# nh-vend_v0_1.net
KiCad netlist of a schematic drawn in EAGLE
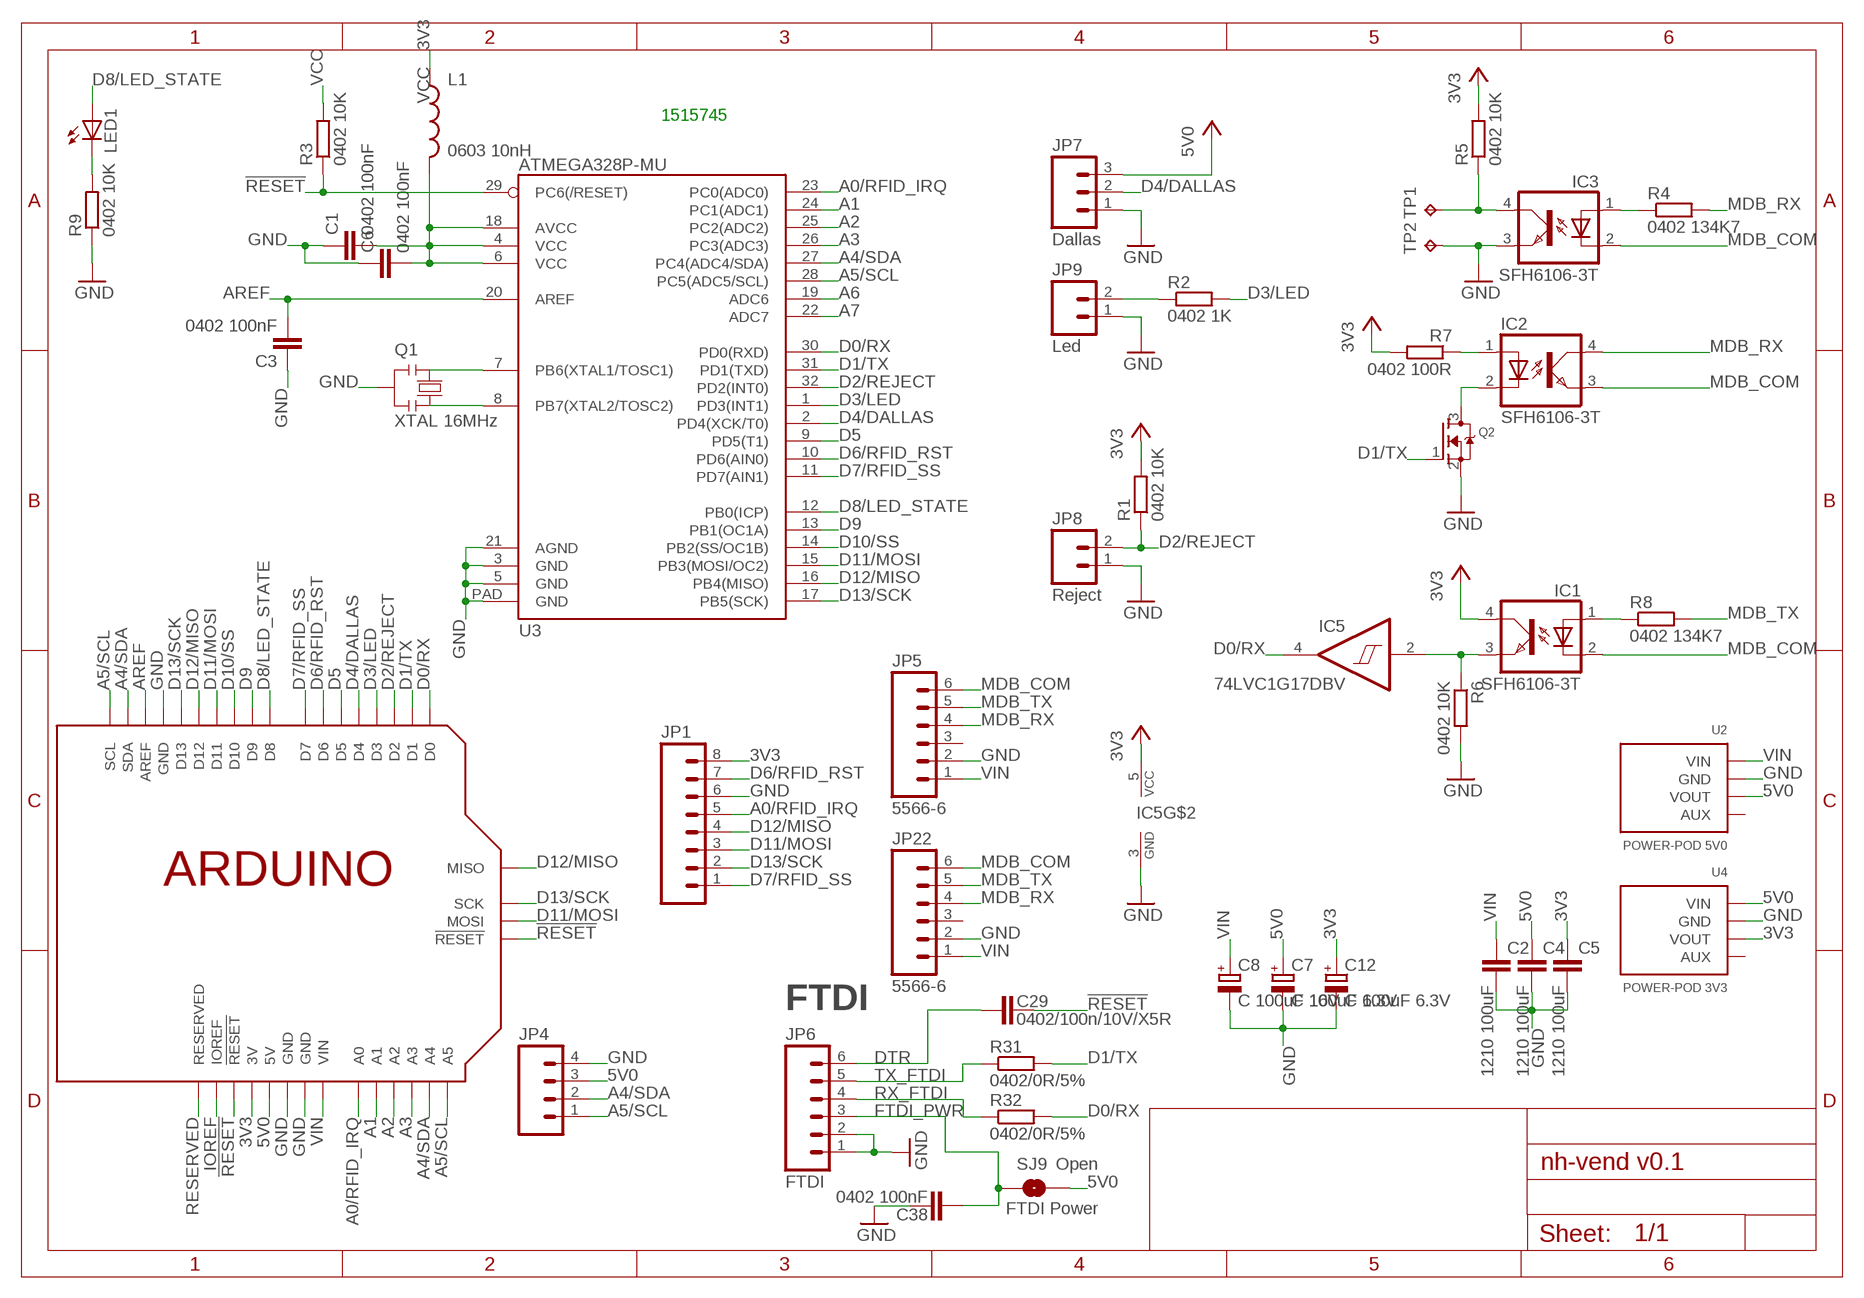
[diagram p0: schematic, sheet 1]

(export (version "E")
  (design (tool "Eeschema 10.0.6"))
  (components
    (comp (ref "C1")
      (value "0402 100nF")
      (footprint "eagle-import:C0402-SMALLER")
      (libsource (lib "eagle-import") (part "C-EUC0402-SMALLER"))
    )
    (comp (ref "C2")
      (value "1210 100uF")
      (footprint "eagle-import:C1210")
      (libsource (lib "eagle-import") (part "C-EUC1210"))
    )
    (comp (ref "C3")
      (value "0402 100nF")
      (footprint "eagle-import:C0402-SMALLER")
      (libsource (lib "eagle-import") (part "C-EUC0402-SMALLER"))
    )
    (comp (ref "C4")
      (value "1210 100uF")
      (footprint "eagle-import:C1210")
      (libsource (lib "eagle-import") (part "C-EUC1210"))
    )
    (comp (ref "C5")
      (value "1210 100uF")
      (footprint "eagle-import:C1210")
      (libsource (lib "eagle-import") (part "C-EUC1210"))
    )
    (comp (ref "C6")
      (value "0402 100nF")
      (footprint "eagle-import:C0402-SMALLER")
      (libsource (lib "eagle-import") (part "C-EUC0402-SMALLER"))
    )
    (comp (ref "C7")
      (value "C 100uF 6.3V")
      (footprint "eagle-import:PANASONIC_C")
      (libsource (lib "eagle-import") (part "CPOL-EUC"))
    )
    (comp (ref "C8")
      (value "C 100uF 16V")
      (footprint "eagle-import:PANASONIC_C")
      (libsource (lib "eagle-import") (part "CPOL-EUC"))
    )
    (comp (ref "C12")
      (value "C 100uF 6.3V")
      (footprint "eagle-import:PANASONIC_C")
      (libsource (lib "eagle-import") (part "CPOL-EUC"))
    )
    (comp (ref "C29")
      (value "0402/100n/10V/X5R")
      (footprint "eagle-import:C0402-ARDUINO-ROUND")
      (libsource (lib "eagle-import") (part "TiLDA Mk2 Parts_C-EUC0402-ARDUINO-ROUND"))
    )
    (comp (ref "C38")
      (value "0402 100nF")
      (footprint "eagle-import:C0402-SMALLER")
      (libsource (lib "eagle-import") (part "TiLDA Mk2 Parts_C-EUC0402-SMALLER"))
    )
    (comp (ref "IC1")
      (value "SFH6106-3T")
      (footprint "eagle-import:SO04")
      (libsource (lib "eagle-import") (part "OPTO-DC"))
    )
    (comp (ref "IC2")
      (value "SFH6106-3T")
      (footprint "eagle-import:SO04")
      (libsource (lib "eagle-import") (part "OPTO-DC"))
    )
    (comp (ref "IC3")
      (value "SFH6106-3T")
      (footprint "eagle-import:SO04")
      (libsource (lib "eagle-import") (part "OPTO-DC"))
    )
    (comp (ref "IC5")
      (value "74LVC1G17DBV")
      (footprint "eagle-import:SOT23-5")
      (libsource (lib "eagle-import") (part "741G17DBVLVC"))
    )
    (comp (ref "JP1")
      (value "M081X08")
      (footprint "eagle-import:1X08")
      (libsource (lib "eagle-import") (part "M081X08"))
    )
    (comp (ref "JP4")
      (value "M04PTH")
      (footprint "eagle-import:1X04")
      (libsource (lib "eagle-import") (part "M04PTH"))
    )
    (comp (ref "JP5")
      (value "5566-6")
      (footprint "eagle-import:5566-6")
      (fields (field (name "MF") "Molex"))
      (libsource (lib "eagle-import") (part "M06-5566"))
    )
    (comp (ref "JP6")
      (value "FTDI")
      (footprint "eagle-import:1X06")
      (libsource (lib "eagle-import") (part "TiLDA Mk2 Parts_M06SIP"))
    )
    (comp (ref "JP7")
      (value "Dallas")
      (footprint "eagle-import:SCREWTERMINAL-5MM-3")
      (libsource (lib "eagle-import") (part "M03-SCREW-5MM"))
    )
    (comp (ref "JP8")
      (value "Reject")
      (footprint "eagle-import:SCREWTERMINAL-5MM-2")
      (libsource (lib "eagle-import") (part "M025MM"))
    )
    (comp (ref "JP9")
      (value "Led")
      (footprint "eagle-import:SCREWTERMINAL-5MM-2")
      (libsource (lib "eagle-import") (part "M025MM"))
    )
    (comp (ref "JP22")
      (value "5566-6")
      (footprint "eagle-import:5566-6")
      (fields (field (name "MF") "Molex"))
      (libsource (lib "eagle-import") (part "M06-5566"))
    )
    (comp (ref "L1")
      (value "0603 10nH")
      (footprint "eagle-import:C0603K-SMALL")
      (libsource (lib "eagle-import") (part "INDUCTOR0603K-SMALL"))
    )
    (comp (ref "LED1")
      (value "LED0805-1206")
      (footprint "eagle-import:LED-0805-1206")
      (libsource (lib "eagle-import") (part "LED0805-1206"))
    )
    (comp (ref "Q1")
      (value "XTAL 16MHz")
      (footprint "eagle-import:RESONATOR")
      (libsource (lib "eagle-import") (part "RESONATORMU"))
    )
    (comp (ref "Q2")
      (value "MOSFET-N-SOT23-SPARK")
      (footprint "eagle-import:SOT23-3")
      (libsource (lib "eagle-import") (part "MOSFET-N-SOT23-SPARK"))
    )
    (comp (ref "R1")
      (value "0402 10K")
      (footprint "eagle-import:R0402-SMALLER")
      (libsource (lib "eagle-import") (part "R-EU_R0402-SMALLER"))
    )
    (comp (ref "R2")
      (value "0402 1K")
      (footprint "eagle-import:R0402-SMALLER")
      (libsource (lib "eagle-import") (part "R-EU_R0402-SMALLER"))
    )
    (comp (ref "R3")
      (value "0402 10K")
      (footprint "eagle-import:R0402-SMALLER")
      (libsource (lib "eagle-import") (part "R-EU_R0402-SMALLER"))
    )
    (comp (ref "R4")
      (value "0402 134K7")
      (footprint "eagle-import:R0402-SMALLER")
      (libsource (lib "eagle-import") (part "R-EU_R0402-SMALLER"))
    )
    (comp (ref "R5")
      (value "0402 10K")
      (footprint "eagle-import:R0402-SMALLER")
      (libsource (lib "eagle-import") (part "R-EU_R0402-SMALLER"))
    )
    (comp (ref "R6")
      (value "0402 10K")
      (footprint "eagle-import:R0402-SMALLER")
      (libsource (lib "eagle-import") (part "R-EU_R0402-SMALLER"))
    )
    (comp (ref "R7")
      (value "0402 100R")
      (footprint "eagle-import:R0402-SMALLER")
      (libsource (lib "eagle-import") (part "R-EU_R0402-SMALLER"))
    )
    (comp (ref "R8")
      (value "0402 134K7")
      (footprint "eagle-import:R0402-SMALLER")
      (libsource (lib "eagle-import") (part "R-EU_R0402-SMALLER"))
    )
    (comp (ref "R9")
      (value "0402 10K")
      (footprint "eagle-import:R0402-SMALLER")
      (libsource (lib "eagle-import") (part "R-EU_R0402-SMALLER"))
    )
    (comp (ref "R31")
      (value "0402/0R/5%")
      (footprint "eagle-import:R0402-ARDUINO-ROUND")
      (libsource (lib "eagle-import") (part "R-EU_R0402-ARDUINO-ROUND"))
    )
    (comp (ref "R32")
      (value "0402/0R/5%")
      (footprint "eagle-import:R0402-ARDUINO-ROUND")
      (libsource (lib "eagle-import") (part "R-EU_R0402-ARDUINO-ROUND"))
    )
    (comp (ref "SJ9")
      (value "FTDI Power")
      (footprint "eagle-import:SJ_2S-NO")
      (libsource (lib "eagle-import") (part "SOLDERJUMPERNO"))
    )
    (comp (ref "TP1")
      (value "TPPAD1-10-ROUND")
      (footprint "eagle-import:P1-10-ROUND-CAN")
      (libsource (lib "eagle-import") (part "TPPAD1-10-ROUND"))
    )
    (comp (ref "TP2")
      (value "TPPAD1-10-ROUND")
      (footprint "eagle-import:P1-10-ROUND-CAN")
      (libsource (lib "eagle-import") (part "TPPAD1-10-ROUND"))
    )
    (comp (ref "U1")
      (value "ARDUINOSPI-REFRENCE")
      (footprint "eagle-import:ARDUINOR3-LWKTXT-REF-SPI")
      (libsource (lib "eagle-import") (part "ARDUINOSPI-REFRENCE"))
    )
    (comp (ref "U2")
      (value "POWER-POD 5V0")
      (footprint "eagle-import:POWER-POD-LANDING")
      (libsource (lib "eagle-import") (part "POWER-POD"))
    )
    (comp (ref "U3")
      (value "ATMEGA328P-MU")
      (footprint "eagle-import:MLF32-SHORT-CREAM")
      (libsource (lib "eagle-import") (part "ATMEGA328-MLF-SHORT"))
    )
    (comp (ref "U4")
      (value "POWER-POD 3V3")
      (footprint "eagle-import:POWER-POD-LANDING")
      (libsource (lib "eagle-import") (part "POWER-POD"))
    )
  )
  (nets
    (net (code "1") (name "/A0{slash}RFID_IRQ") (class "Default")
      (node (ref "JP1") (pin "5") (pinfunction "5_5") (pintype "passive"))
      (node (ref "U1") (pin "A0") (pinfunction "A0_A0") (pintype "bidirectional"))
      (node (ref "U3") (pin "23") (pinfunction "PC0(ADC0)_23") (pintype "bidirectional"))
    )
    (net (code "2") (name "/A1") (class "Default")
      (node (ref "U1") (pin "A1") (pinfunction "A1_A1") (pintype "bidirectional"))
      (node (ref "U3") (pin "24") (pinfunction "PC1(ADC1)_24") (pintype "bidirectional"))
    )
    (net (code "3") (name "/A2") (class "Default")
      (node (ref "U1") (pin "A2") (pinfunction "A2_A2") (pintype "bidirectional"))
      (node (ref "U3") (pin "25") (pinfunction "PC2(ADC2)_25") (pintype "bidirectional"))
    )
    (net (code "4") (name "/A3") (class "Default")
      (node (ref "U1") (pin "A3") (pinfunction "A3_A3") (pintype "bidirectional"))
      (node (ref "U3") (pin "26") (pinfunction "PC3(ADC3)_26") (pintype "bidirectional"))
    )
    (net (code "5") (name "/A4{slash}SDA") (class "Default")
      (node (ref "JP4") (pin "2") (pinfunction "2_2") (pintype "passive"))
      (node (ref "U1") (pin "A4") (pinfunction "A4_A4") (pintype "bidirectional"))
      (node (ref "U1") (pin "SDA") (pinfunction "SDA_SDA") (pintype "bidirectional"))
      (node (ref "U3") (pin "27") (pinfunction "PC4(ADC4/SDA)_27") (pintype "bidirectional"))
    )
    (net (code "6") (name "/A5{slash}SCL") (class "Default")
      (node (ref "JP4") (pin "1") (pinfunction "1_1") (pintype "passive"))
      (node (ref "U1") (pin "A5") (pinfunction "A5_A5") (pintype "bidirectional"))
      (node (ref "U1") (pin "SCL") (pinfunction "SCL_SCL") (pintype "bidirectional"))
      (node (ref "U3") (pin "28") (pinfunction "PC5(ADC5/SCL)_28") (pintype "bidirectional"))
    )
    (net (code "7") (name "/A6") (class "Default")
      (node (ref "U3") (pin "19") (pinfunction "ADC6_19") (pintype "bidirectional"))
    )
    (net (code "8") (name "/A7") (class "Default")
      (node (ref "U3") (pin "22") (pinfunction "ADC7_22") (pintype "bidirectional"))
    )
    (net (code "9") (name "/AREF") (class "Default")
      (node (ref "C3") (pin "2") (pinfunction "2_2") (pintype "passive"))
      (node (ref "U1") (pin "AREF") (pinfunction "AREF_AREF") (pintype "bidirectional"))
      (node (ref "U3") (pin "20") (pinfunction "AREF_20") (pintype "bidirectional"))
    )
    (net (code "10") (name "/D0{slash}RX") (class "Default")
      (node (ref "IC5") (pin "4") (pinfunction "O_4") (pintype "output"))
      (node (ref "R32") (pin "2") (pinfunction "2_2") (pintype "passive"))
      (node (ref "U1") (pin "D0") (pinfunction "D0_D0") (pintype "bidirectional"))
      (node (ref "U3") (pin "30") (pinfunction "PD0(RXD)_30") (pintype "bidirectional"))
    )
    (net (code "11") (name "/D1{slash}TX") (class "Default")
      (node (ref "Q2") (pin "1") (pinfunction "G_1") (pintype "bidirectional"))
      (node (ref "R31") (pin "2") (pinfunction "2_2") (pintype "passive"))
      (node (ref "U1") (pin "D1") (pinfunction "D1_D1") (pintype "bidirectional"))
      (node (ref "U3") (pin "31") (pinfunction "PD1(TXD)_31") (pintype "bidirectional"))
    )
    (net (code "12") (name "/D2{slash}REJECT") (class "Default")
      (node (ref "JP8") (pin "2") (pinfunction "2_2") (pintype "passive"))
      (node (ref "R1") (pin "1") (pinfunction "1_1") (pintype "passive"))
      (node (ref "U1") (pin "D2") (pinfunction "D2_D2") (pintype "bidirectional"))
      (node (ref "U3") (pin "32") (pinfunction "PD2(INT0)_32") (pintype "bidirectional"))
    )
    (net (code "13") (name "/D3{slash}LED") (class "Default")
      (node (ref "R2") (pin "2") (pinfunction "2_2") (pintype "passive"))
      (node (ref "U1") (pin "D3") (pinfunction "D3_D3") (pintype "bidirectional"))
      (node (ref "U3") (pin "1") (pinfunction "PD3(INT1)_1") (pintype "bidirectional"))
    )
    (net (code "14") (name "/D4{slash}DALLAS") (class "Default")
      (node (ref "JP7") (pin "2") (pinfunction "2_2") (pintype "passive"))
      (node (ref "U1") (pin "D4") (pinfunction "D4_D4") (pintype "bidirectional"))
      (node (ref "U3") (pin "2") (pinfunction "PD4(XCK/T0)_2") (pintype "bidirectional"))
    )
    (net (code "15") (name "/D5") (class "Default")
      (node (ref "U1") (pin "D5") (pinfunction "D5_D5") (pintype "bidirectional"))
      (node (ref "U3") (pin "9") (pinfunction "PD5(T1)_9") (pintype "bidirectional"))
    )
    (net (code "16") (name "/D6{slash}RFID_RST") (class "Default")
      (node (ref "JP1") (pin "7") (pinfunction "7_7") (pintype "passive"))
      (node (ref "U1") (pin "D6") (pinfunction "D6_D6") (pintype "bidirectional"))
      (node (ref "U3") (pin "10") (pinfunction "PD6(AIN0)_10") (pintype "bidirectional"))
    )
    (net (code "17") (name "/D7{slash}RFID_SS") (class "Default")
      (node (ref "JP1") (pin "1") (pinfunction "1_1") (pintype "passive"))
      (node (ref "U1") (pin "D7") (pinfunction "D7_D7") (pintype "bidirectional"))
      (node (ref "U3") (pin "11") (pinfunction "PD7(AIN1)_11") (pintype "bidirectional"))
    )
    (net (code "18") (name "/D8{slash}LED_STATE") (class "Default")
      (node (ref "LED1") (pin "A") (pinfunction "A_A") (pintype "passive"))
      (node (ref "U1") (pin "D8") (pinfunction "D8_D8") (pintype "bidirectional"))
      (node (ref "U3") (pin "12") (pinfunction "PB0(ICP)_12") (pintype "bidirectional"))
    )
    (net (code "19") (name "/D9") (class "Default")
      (node (ref "U1") (pin "D9") (pinfunction "D9_D9") (pintype "bidirectional"))
      (node (ref "U3") (pin "13") (pinfunction "PB1(OC1A)_13") (pintype "bidirectional"))
    )
    (net (code "20") (name "/D10{slash}SS") (class "Default")
      (node (ref "U1") (pin "D10") (pinfunction "D10_D10") (pintype "bidirectional"))
      (node (ref "U3") (pin "14") (pinfunction "PB2(SS/OC1B)_14") (pintype "bidirectional"))
    )
    (net (code "21") (name "/D11{slash}MOSI") (class "Default")
      (node (ref "JP1") (pin "3") (pinfunction "3_3") (pintype "passive"))
      (node (ref "U1") (pin "D11") (pinfunction "D11_D11") (pintype "bidirectional"))
      (node (ref "U1") (pin "MOSI") (pinfunction "MOSI_MOSI") (pintype "bidirectional"))
      (node (ref "U3") (pin "15") (pinfunction "PB3(MOSI/OC2)_15") (pintype "bidirectional"))
    )
    (net (code "22") (name "/D12{slash}MISO") (class "Default")
      (node (ref "JP1") (pin "4") (pinfunction "4_4") (pintype "passive"))
      (node (ref "U1") (pin "D12") (pinfunction "D12_D12") (pintype "bidirectional"))
      (node (ref "U1") (pin "MISO") (pinfunction "MISO_MISO") (pintype "bidirectional"))
      (node (ref "U3") (pin "16") (pinfunction "PB4(MISO)_16") (pintype "bidirectional"))
    )
    (net (code "23") (name "/D13{slash}SCK") (class "Default")
      (node (ref "JP1") (pin "2") (pinfunction "2_2") (pintype "passive"))
      (node (ref "U1") (pin "D13") (pinfunction "D13_D13") (pintype "bidirectional"))
      (node (ref "U1") (pin "SCK") (pinfunction "SCK_SCK") (pintype "bidirectional"))
      (node (ref "U3") (pin "17") (pinfunction "PB5(SCK)_17") (pintype "bidirectional"))
    )
    (net (code "24") (name "/DTR") (class "Default")
      (node (ref "C29") (pin "2") (pinfunction "2_2") (pintype "passive"))
      (node (ref "JP6") (pin "6") (pinfunction "6_6") (pintype "passive"))
    )
    (net (code "25") (name "/FTDI_PWR") (class "Default")
      (node (ref "C38") (pin "2") (pinfunction "2_2") (pintype "passive"))
      (node (ref "JP6") (pin "3") (pinfunction "3_3") (pintype "passive"))
      (node (ref "SJ9") (pin "1") (pinfunction "1_1") (pintype "passive"))
    )
    (net (code "26") (name "/IOREF") (class "Default")
      (node (ref "U1") (pin "IOREF") (pinfunction "IOREF_IOREF") (pintype "output"))
    )
    (net (code "27") (name "/MDB_COM") (class "Default")
      (node (ref "IC1") (pin "2") (pinfunction "C_2") (pintype "passive"))
      (node (ref "IC2") (pin "3") (pinfunction "EMIT_3") (pintype "passive"))
      (node (ref "IC3") (pin "2") (pinfunction "C_2") (pintype "passive"))
      (node (ref "JP22") (pin "6") (pinfunction "6_6") (pintype "passive"))
      (node (ref "JP5") (pin "6") (pinfunction "6_6") (pintype "passive"))
    )
    (net (code "28") (name "/MDB_RX") (class "Default")
      (node (ref "IC2") (pin "4") (pinfunction "COL_4") (pintype "passive"))
      (node (ref "JP22") (pin "4") (pinfunction "4_4") (pintype "passive"))
      (node (ref "JP5") (pin "4") (pinfunction "4_4") (pintype "passive"))
      (node (ref "R4") (pin "2") (pinfunction "2_2") (pintype "passive"))
    )
    (net (code "29") (name "/MDB_TX") (class "Default")
      (node (ref "JP22") (pin "5") (pinfunction "5_5") (pintype "passive"))
      (node (ref "JP5") (pin "5") (pinfunction "5_5") (pintype "passive"))
      (node (ref "R8") (pin "2") (pinfunction "2_2") (pintype "passive"))
    )
    (net (code "31") (name "/RX_FTDI") (class "Default")
      (node (ref "JP6") (pin "4") (pinfunction "4_4") (pintype "passive"))
      (node (ref "R32") (pin "1") (pinfunction "1_1") (pintype "passive"))
    )
    (net (code "32") (name "/TX_FTDI") (class "Default")
      (node (ref "JP6") (pin "5") (pinfunction "5_5") (pintype "passive"))
      (node (ref "R31") (pin "1") (pinfunction "1_1") (pintype "passive"))
    )
    (net (code "33") (name "/VCC") (class "Default")
      (node (ref "C1") (pin "2") (pinfunction "2_2") (pintype "passive"))
      (node (ref "C6") (pin "2") (pinfunction "2_2") (pintype "passive"))
      (node (ref "L1") (pin "2") (pinfunction "2_2") (pintype "passive"))
      (node (ref "R3") (pin "2") (pinfunction "2_2") (pintype "passive"))
      (node (ref "U3") (pin "18") (pinfunction "AVCC_18") (pintype "bidirectional"))
      (node (ref "U3") (pin "4") (pinfunction "VCC_4") (pintype "bidirectional"))
      (node (ref "U3") (pin "6") (pinfunction "VCC_6") (pintype "bidirectional"))
    )
    (net (code "34") (name "/VIN") (class "Default")
      (node (ref "C2") (pin "1") (pinfunction "1_1") (pintype "passive"))
      (node (ref "C8") (pin "+") (pinfunction "+_+") (pintype "passive"))
      (node (ref "JP22") (pin "1") (pinfunction "1_1") (pintype "passive"))
      (node (ref "JP5") (pin "1") (pinfunction "1_1") (pintype "passive"))
      (node (ref "U1") (pin "VIN") (pinfunction "VIN_VIN") (pintype "power_in"))
      (node (ref "U2") (pin "1") (pinfunction "VIN_1") (pintype "bidirectional"))
    )
    (net (code "35") (name "/~{RESET}") (class "Default")
      (node (ref "C29") (pin "1") (pinfunction "1_1") (pintype "passive"))
      (node (ref "R3") (pin "1") (pinfunction "1_1") (pintype "passive"))
      (node (ref "U1") (pin "!RESET") (pinfunction "~{RESET}_!RESET") (pintype "bidirectional"))
      (node (ref "U1") (pin "!RESET@ISP") (pinfunction "~{RESET}_!RESET@ISP") (pintype "bidirectional"))
      (node (ref "U3") (pin "29") (pinfunction "PC6(/RESET)_29") (pintype "bidirectional"))
    )
    (net (code "36") (name "3V3") (class "Default")
      (node (ref "C12") (pin "+") (pinfunction "+_+") (pintype "passive"))
      (node (ref "C5") (pin "1") (pinfunction "1_1") (pintype "passive"))
      (node (ref "IC1") (pin "4") (pinfunction "COL_4") (pintype "passive"))
      (node (ref "IC5") (pin "5") (pinfunction "VCC_5") (pintype "power_in"))
      (node (ref "JP1") (pin "8") (pinfunction "8_8") (pintype "passive"))
      (node (ref "L1") (pin "1") (pinfunction "1_1") (pintype "passive"))
      (node (ref "R1") (pin "2") (pinfunction "2_2") (pintype "passive"))
      (node (ref "R5") (pin "2") (pinfunction "2_2") (pintype "passive"))
      (node (ref "R7") (pin "2") (pinfunction "2_2") (pintype "passive"))
      (node (ref "U1") (pin "3V") (pinfunction "3V_3V") (pintype "power_in"))
      (node (ref "U4") (pin "3") (pinfunction "VOUT_3") (pintype "bidirectional"))
    )
    (net (code "37") (name "5V0") (class "Default")
      (node (ref "C4") (pin "1") (pinfunction "1_1") (pintype "passive"))
      (node (ref "C7") (pin "+") (pinfunction "+_+") (pintype "passive"))
      (node (ref "JP4") (pin "3") (pinfunction "3_3") (pintype "passive"))
      (node (ref "JP7") (pin "3") (pinfunction "3_3") (pintype "passive"))
      (node (ref "SJ9") (pin "2") (pinfunction "2_2") (pintype "passive"))
      (node (ref "U1") (pin "5V") (pinfunction "5V_5V") (pintype "power_in"))
      (node (ref "U1") (pin "5V@ISP") (pinfunction "5V_5V@ISP") (pintype "power_in"))
      (node (ref "U2") (pin "3") (pinfunction "VOUT_3") (pintype "bidirectional"))
      (node (ref "U4") (pin "1") (pinfunction "VIN_1") (pintype "bidirectional"))
    )
    (net (code "38") (name "GND") (class "Default")
      (node (ref "C1") (pin "1") (pinfunction "1_1") (pintype "passive"))
      (node (ref "C12") (pin "-") (pinfunction "-_-") (pintype "passive"))
      (node (ref "C2") (pin "2") (pinfunction "2_2") (pintype "passive"))
      (node (ref "C3") (pin "1") (pinfunction "1_1") (pintype "passive"))
      (node (ref "C38") (pin "1") (pinfunction "1_1") (pintype "passive"))
      (node (ref "C4") (pin "2") (pinfunction "2_2") (pintype "passive"))
      (node (ref "C5") (pin "2") (pinfunction "2_2") (pintype "passive"))
      (node (ref "C6") (pin "1") (pinfunction "1_1") (pintype "passive"))
      (node (ref "C7") (pin "-") (pinfunction "-_-") (pintype "passive"))
      (node (ref "C8") (pin "-") (pinfunction "-_-") (pintype "passive"))
      (node (ref "IC3") (pin "3") (pinfunction "EMIT_3") (pintype "passive"))
      (node (ref "IC5") (pin "3") (pinfunction "GND_3") (pintype "power_in"))
      (node (ref "JP1") (pin "6") (pinfunction "6_6") (pintype "passive"))
      (node (ref "JP22") (pin "2") (pinfunction "2_2") (pintype "passive"))
      (node (ref "JP4") (pin "4") (pinfunction "4_4") (pintype "passive"))
      (node (ref "JP5") (pin "2") (pinfunction "2_2") (pintype "passive"))
      (node (ref "JP6") (pin "1") (pinfunction "1_1") (pintype "passive"))
      (node (ref "JP6") (pin "2") (pinfunction "2_2") (pintype "passive"))
      (node (ref "JP7") (pin "1") (pinfunction "1_1") (pintype "passive"))
      (node (ref "JP8") (pin "1") (pinfunction "1_1") (pintype "passive"))
      (node (ref "JP9") (pin "1") (pinfunction "1_1") (pintype "passive"))
      (node (ref "Q1") (pin "2") (pinfunction "2_2") (pintype "passive"))
      (node (ref "Q2") (pin "2") (pinfunction "S_2") (pintype "bidirectional"))
      (node (ref "R6") (pin "2") (pinfunction "2_2") (pintype "passive"))
      (node (ref "R9") (pin "1") (pinfunction "1_1") (pintype "passive"))
      (node (ref "TP2") (pin "TP") (pinfunction "TP_TP") (pintype "input"))
      (node (ref "U1") (pin "GND@1") (pinfunction "GND_GND@1") (pintype "power_in"))
      (node (ref "U1") (pin "GND@2") (pinfunction "GND_GND@2") (pintype "power_in"))
      (node (ref "U1") (pin "GND@3") (pinfunction "GND_GND@3") (pintype "power_in"))
      (node (ref "U1") (pin "GND@ISP") (pinfunction "GND_GND@ISP") (pintype "power_in"))
      (node (ref "U2") (pin "2") (pinfunction "GND_2") (pintype "bidirectional"))
      (node (ref "U3") (pin "21") (pinfunction "AGND_21") (pintype "bidirectional"))
      (node (ref "U3") (pin "3") (pinfunction "GND_3") (pintype "bidirectional"))
      (node (ref "U3") (pin "5") (pinfunction "GND_5") (pintype "bidirectional"))
      (node (ref "U3") (pin "PAD") (pinfunction "GND_PAD") (pintype "bidirectional"))
      (node (ref "U4") (pin "2") (pinfunction "GND_2") (pintype "bidirectional"))
    )
    (net (code "39") (name "Net-(IC1-A)") (class "Default")
      (node (ref "IC1") (pin "1") (pinfunction "A_1") (pintype "passive"))
      (node (ref "R8") (pin "1") (pinfunction "1_1") (pintype "passive"))
    )
    (net (code "40") (name "Net-(IC1-EMIT)") (class "Default")
      (node (ref "IC1") (pin "3") (pinfunction "EMIT_3") (pintype "passive"))
      (node (ref "IC5") (pin "2") (pinfunction "I_2") (pintype "input"))
      (node (ref "R6") (pin "1") (pinfunction "1_1") (pintype "passive"))
    )
    (net (code "41") (name "Net-(IC2-A)") (class "Default")
      (node (ref "IC2") (pin "1") (pinfunction "A_1") (pintype "passive"))
      (node (ref "R7") (pin "1") (pinfunction "1_1") (pintype "passive"))
    )
    (net (code "42") (name "Net-(IC2-C)") (class "Default")
      (node (ref "IC2") (pin "2") (pinfunction "C_2") (pintype "passive"))
      (node (ref "Q2") (pin "3") (pinfunction "D_3") (pintype "bidirectional"))
    )
    (net (code "43") (name "Net-(IC3-A)") (class "Default")
      (node (ref "IC3") (pin "1") (pinfunction "A_1") (pintype "passive"))
      (node (ref "R4") (pin "1") (pinfunction "1_1") (pintype "passive"))
    )
    (net (code "44") (name "Net-(IC3-COL)") (class "Default")
      (node (ref "IC3") (pin "4") (pinfunction "COL_4") (pintype "passive"))
      (node (ref "R5") (pin "1") (pinfunction "1_1") (pintype "passive"))
      (node (ref "TP1") (pin "TP") (pinfunction "TP_TP") (pintype "input"))
    )
    (net (code "45") (name "Net-(JP9-Pad2)") (class "Default")
      (node (ref "JP9") (pin "2") (pinfunction "2_2") (pintype "passive"))
      (node (ref "R2") (pin "1") (pinfunction "1_1") (pintype "passive"))
    )
    (net (code "46") (name "Net-(LED1-PadC)") (class "Default")
      (node (ref "LED1") (pin "C") (pinfunction "C_C") (pintype "passive"))
      (node (ref "R9") (pin "2") (pinfunction "2_2") (pintype "passive"))
    )
    (net (code "47") (name "Net-(U3-PB6(XTAL1{slash}TOSC1))") (class "Default")
      (node (ref "Q1") (pin "1") (pinfunction "1_1") (pintype "passive"))
      (node (ref "U3") (pin "7") (pinfunction "PB6(XTAL1/TOSC1)_7") (pintype "bidirectional"))
    )
    (net (code "48") (name "Net-(U3-PB7(XTAL2{slash}TOSC2))") (class "Default")
      (node (ref "Q1") (pin "3") (pinfunction "3_3") (pintype "passive"))
      (node (ref "U3") (pin "8") (pinfunction "PB7(XTAL2/TOSC2)_8") (pintype "bidirectional"))
    )
    (net (code "49") (name "unconnected-(JP5-Pad3)") (class "Default")
      (node (ref "JP5") (pin "3") (pinfunction "3_3") (pintype "passive"))
    )
    (net (code "50") (name "unconnected-(JP22-Pad3)") (class "Default")
      (node (ref "JP22") (pin "3") (pinfunction "3_3") (pintype "passive"))
    )
    (net (code "51") (name "unconnected-(U1-PadRESERVED)") (class "Default")
      (node (ref "U1") (pin "RESERVED") (pinfunction "RESERVED_RESERVED") (pintype "no_connect"))
    )
    (net (code "52") (name "unconnected-(U2-AUX-Pad4)") (class "Default")
      (node (ref "U2") (pin "4") (pinfunction "AUX_4") (pintype "bidirectional"))
    )
    (net (code "53") (name "unconnected-(U4-AUX-Pad4)") (class "Default")
      (node (ref "U4") (pin "4") (pinfunction "AUX_4") (pintype "bidirectional"))
    )
  )
)
